# L298N.net
KiCad netlist of a schematic drawn in EAGLE
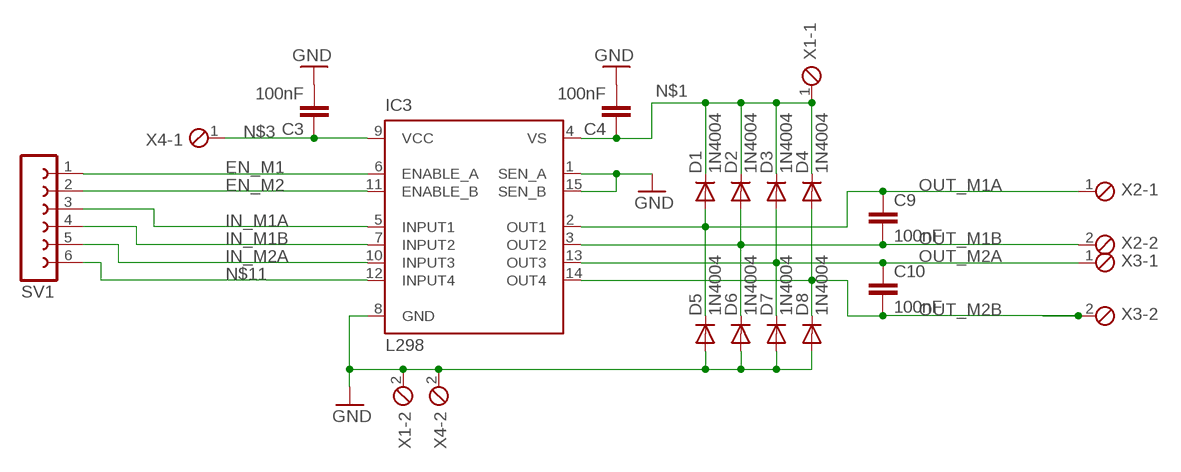
[diagram p0: schematic, sheet 1]

(export (version "E")
  (design (tool "Eeschema 10.0.6"))
  (components
    (comp (ref "C3")
      (value "100nF")
      (footprint "eagle-import:C050-050X075")
      (libsource (lib "eagle-import") (part "C-EU050-050X075"))
    )
    (comp (ref "C4")
      (value "100nF")
      (footprint "eagle-import:C050-050X075")
      (libsource (lib "eagle-import") (part "C-EU050-050X075"))
    )
    (comp (ref "C9")
      (value "100nF")
      (footprint "eagle-import:C050-050X075")
      (libsource (lib "eagle-import") (part "C-EU050-050X075"))
    )
    (comp (ref "C10")
      (value "100nF")
      (footprint "eagle-import:C050-050X075")
      (libsource (lib "eagle-import") (part "C-EU050-050X075"))
    )
    (comp (ref "D1")
      (value "1N4004")
      (footprint "eagle-import:DO41-10")
      (libsource (lib "eagle-import") (part "1N4004"))
    )
    (comp (ref "D2")
      (value "1N4004")
      (footprint "eagle-import:DO41-10")
      (libsource (lib "eagle-import") (part "1N4004"))
    )
    (comp (ref "D3")
      (value "1N4004")
      (footprint "eagle-import:DO41-10")
      (libsource (lib "eagle-import") (part "1N4004"))
    )
    (comp (ref "D4")
      (value "1N4004")
      (footprint "eagle-import:DO41-10")
      (libsource (lib "eagle-import") (part "1N4004"))
    )
    (comp (ref "D5")
      (value "1N4004")
      (footprint "eagle-import:DO41-10")
      (libsource (lib "eagle-import") (part "1N4004"))
    )
    (comp (ref "D6")
      (value "1N4004")
      (footprint "eagle-import:DO41-10")
      (libsource (lib "eagle-import") (part "1N4004"))
    )
    (comp (ref "D7")
      (value "1N4004")
      (footprint "eagle-import:DO41-10")
      (libsource (lib "eagle-import") (part "1N4004"))
    )
    (comp (ref "D8")
      (value "1N4004")
      (footprint "eagle-import:DO41-10")
      (libsource (lib "eagle-import") (part "1N4004"))
    )
    (comp (ref "IC3")
      (value "L298")
      (footprint "eagle-import:MULTIWATT-15")
      (fields (field (name "MPN") "L298N"))
      (libsource (lib "eagle-import") (part "L298"))
    )
    (comp (ref "SV1")
      (value "FE06-1")
      (footprint "eagle-import:FE06")
      (libsource (lib "eagle-import") (part "FE06-1"))
    )
    (comp (ref "X1")
      (value "MPT2")
      (footprint "eagle-import:2POL254")
      (libsource (lib "eagle-import") (part "MPT2"))
    )
    (comp (ref "X2")
      (value "MPT2")
      (footprint "eagle-import:2POL254")
      (libsource (lib "eagle-import") (part "MPT2"))
    )
    (comp (ref "X3")
      (value "MPT2")
      (footprint "eagle-import:2POL254")
      (libsource (lib "eagle-import") (part "MPT2"))
    )
    (comp (ref "X4")
      (value "MPT2")
      (footprint "eagle-import:2POL254")
      (libsource (lib "eagle-import") (part "MPT2"))
    )
  )
  (nets
    (net (code "1") (name "/EN_M1") (class "Default")
      (node (ref "IC3") (pin "6") (pinfunction "ENABLE_A_6") (pintype "input"))
      (node (ref "SV1") (pin "1") (pinfunction "1_1") (pintype "passive"))
    )
    (net (code "2") (name "/EN_M2") (class "Default")
      (node (ref "IC3") (pin "11") (pinfunction "ENABLE_B_11") (pintype "input"))
      (node (ref "SV1") (pin "2") (pinfunction "2_2") (pintype "passive"))
    )
    (net (code "3") (name "/IN_M1A") (class "Default")
      (node (ref "IC3") (pin "5") (pinfunction "INPUT1_5") (pintype "input"))
      (node (ref "SV1") (pin "3") (pinfunction "3_3") (pintype "passive"))
    )
    (net (code "4") (name "/IN_M1B") (class "Default")
      (node (ref "IC3") (pin "7") (pinfunction "INPUT2_7") (pintype "input"))
      (node (ref "SV1") (pin "4") (pinfunction "4_4") (pintype "passive"))
    )
    (net (code "5") (name "/IN_M2A") (class "Default")
      (node (ref "IC3") (pin "10") (pinfunction "INPUT3_10") (pintype "input"))
      (node (ref "SV1") (pin "5") (pinfunction "5_5") (pintype "passive"))
    )
    (net (code "6") (name "/N$1") (class "Default")
      (node (ref "C4") (pin "1") (pinfunction "1_1") (pintype "passive"))
      (node (ref "D1") (pin "C") (pinfunction "C_C") (pintype "passive"))
      (node (ref "D2") (pin "C") (pinfunction "C_C") (pintype "passive"))
      (node (ref "D3") (pin "C") (pinfunction "C_C") (pintype "passive"))
      (node (ref "D4") (pin "C") (pinfunction "C_C") (pintype "passive"))
      (node (ref "IC3") (pin "4") (pinfunction "VS_4") (pintype "power_in"))
      (node (ref "X1") (pin "1") (pinfunction "1_1") (pintype "passive"))
    )
    (net (code "7") (name "/N$3") (class "Default")
      (node (ref "C3") (pin "1") (pinfunction "1_1") (pintype "passive"))
      (node (ref "IC3") (pin "9") (pinfunction "VCC_9") (pintype "power_in"))
      (node (ref "X4") (pin "1") (pinfunction "1_1") (pintype "passive"))
    )
    (net (code "8") (name "/N$11") (class "Default")
      (node (ref "IC3") (pin "12") (pinfunction "INPUT4_12") (pintype "input"))
      (node (ref "SV1") (pin "6") (pinfunction "6_6") (pintype "passive"))
    )
    (net (code "9") (name "/OUT_M1A") (class "Default")
      (node (ref "C9") (pin "1") (pinfunction "1_1") (pintype "passive"))
      (node (ref "D1") (pin "A") (pinfunction "A_A") (pintype "passive"))
      (node (ref "D5") (pin "C") (pinfunction "C_C") (pintype "passive"))
      (node (ref "IC3") (pin "2") (pinfunction "OUT1_2") (pintype "output"))
      (node (ref "X2") (pin "1") (pinfunction "1_1") (pintype "passive"))
    )
    (net (code "10") (name "/OUT_M1B") (class "Default")
      (node (ref "C9") (pin "2") (pinfunction "2_2") (pintype "passive"))
      (node (ref "D2") (pin "A") (pinfunction "A_A") (pintype "passive"))
      (node (ref "D6") (pin "C") (pinfunction "C_C") (pintype "passive"))
      (node (ref "IC3") (pin "3") (pinfunction "OUT2_3") (pintype "output"))
      (node (ref "X2") (pin "2") (pinfunction "1_2") (pintype "passive"))
    )
    (net (code "11") (name "/OUT_M2A") (class "Default")
      (node (ref "C10") (pin "1") (pinfunction "1_1") (pintype "passive"))
      (node (ref "D3") (pin "A") (pinfunction "A_A") (pintype "passive"))
      (node (ref "D7") (pin "C") (pinfunction "C_C") (pintype "passive"))
      (node (ref "IC3") (pin "13") (pinfunction "OUT3_13") (pintype "output"))
      (node (ref "X3") (pin "1") (pinfunction "1_1") (pintype "passive"))
    )
    (net (code "12") (name "/OUT_M2B") (class "Default")
      (node (ref "C10") (pin "2") (pinfunction "2_2") (pintype "passive"))
      (node (ref "D4") (pin "A") (pinfunction "A_A") (pintype "passive"))
      (node (ref "D8") (pin "C") (pinfunction "C_C") (pintype "passive"))
      (node (ref "IC3") (pin "14") (pinfunction "OUT4_14") (pintype "output"))
      (node (ref "X3") (pin "2") (pinfunction "1_2") (pintype "passive"))
    )
    (net (code "13") (name "GND") (class "Default")
      (node (ref "C3") (pin "2") (pinfunction "2_2") (pintype "passive"))
      (node (ref "C4") (pin "2") (pinfunction "2_2") (pintype "passive"))
      (node (ref "D5") (pin "A") (pinfunction "A_A") (pintype "passive"))
      (node (ref "D6") (pin "A") (pinfunction "A_A") (pintype "passive"))
      (node (ref "D7") (pin "A") (pinfunction "A_A") (pintype "passive"))
      (node (ref "D8") (pin "A") (pinfunction "A_A") (pintype "passive"))
      (node (ref "IC3") (pin "1") (pinfunction "SEN_A_1") (pintype "input"))
      (node (ref "IC3") (pin "15") (pinfunction "SEN_B_15") (pintype "input"))
      (node (ref "IC3") (pin "8") (pinfunction "GND_8") (pintype "power_in"))
      (node (ref "X1") (pin "2") (pinfunction "1_2") (pintype "passive"))
      (node (ref "X4") (pin "2") (pinfunction "1_2") (pintype "passive"))
    )
  )
)
